# PLA_LED_Gen2_Rev4.net
KiCad netlist of a schematic drawn in EAGLE
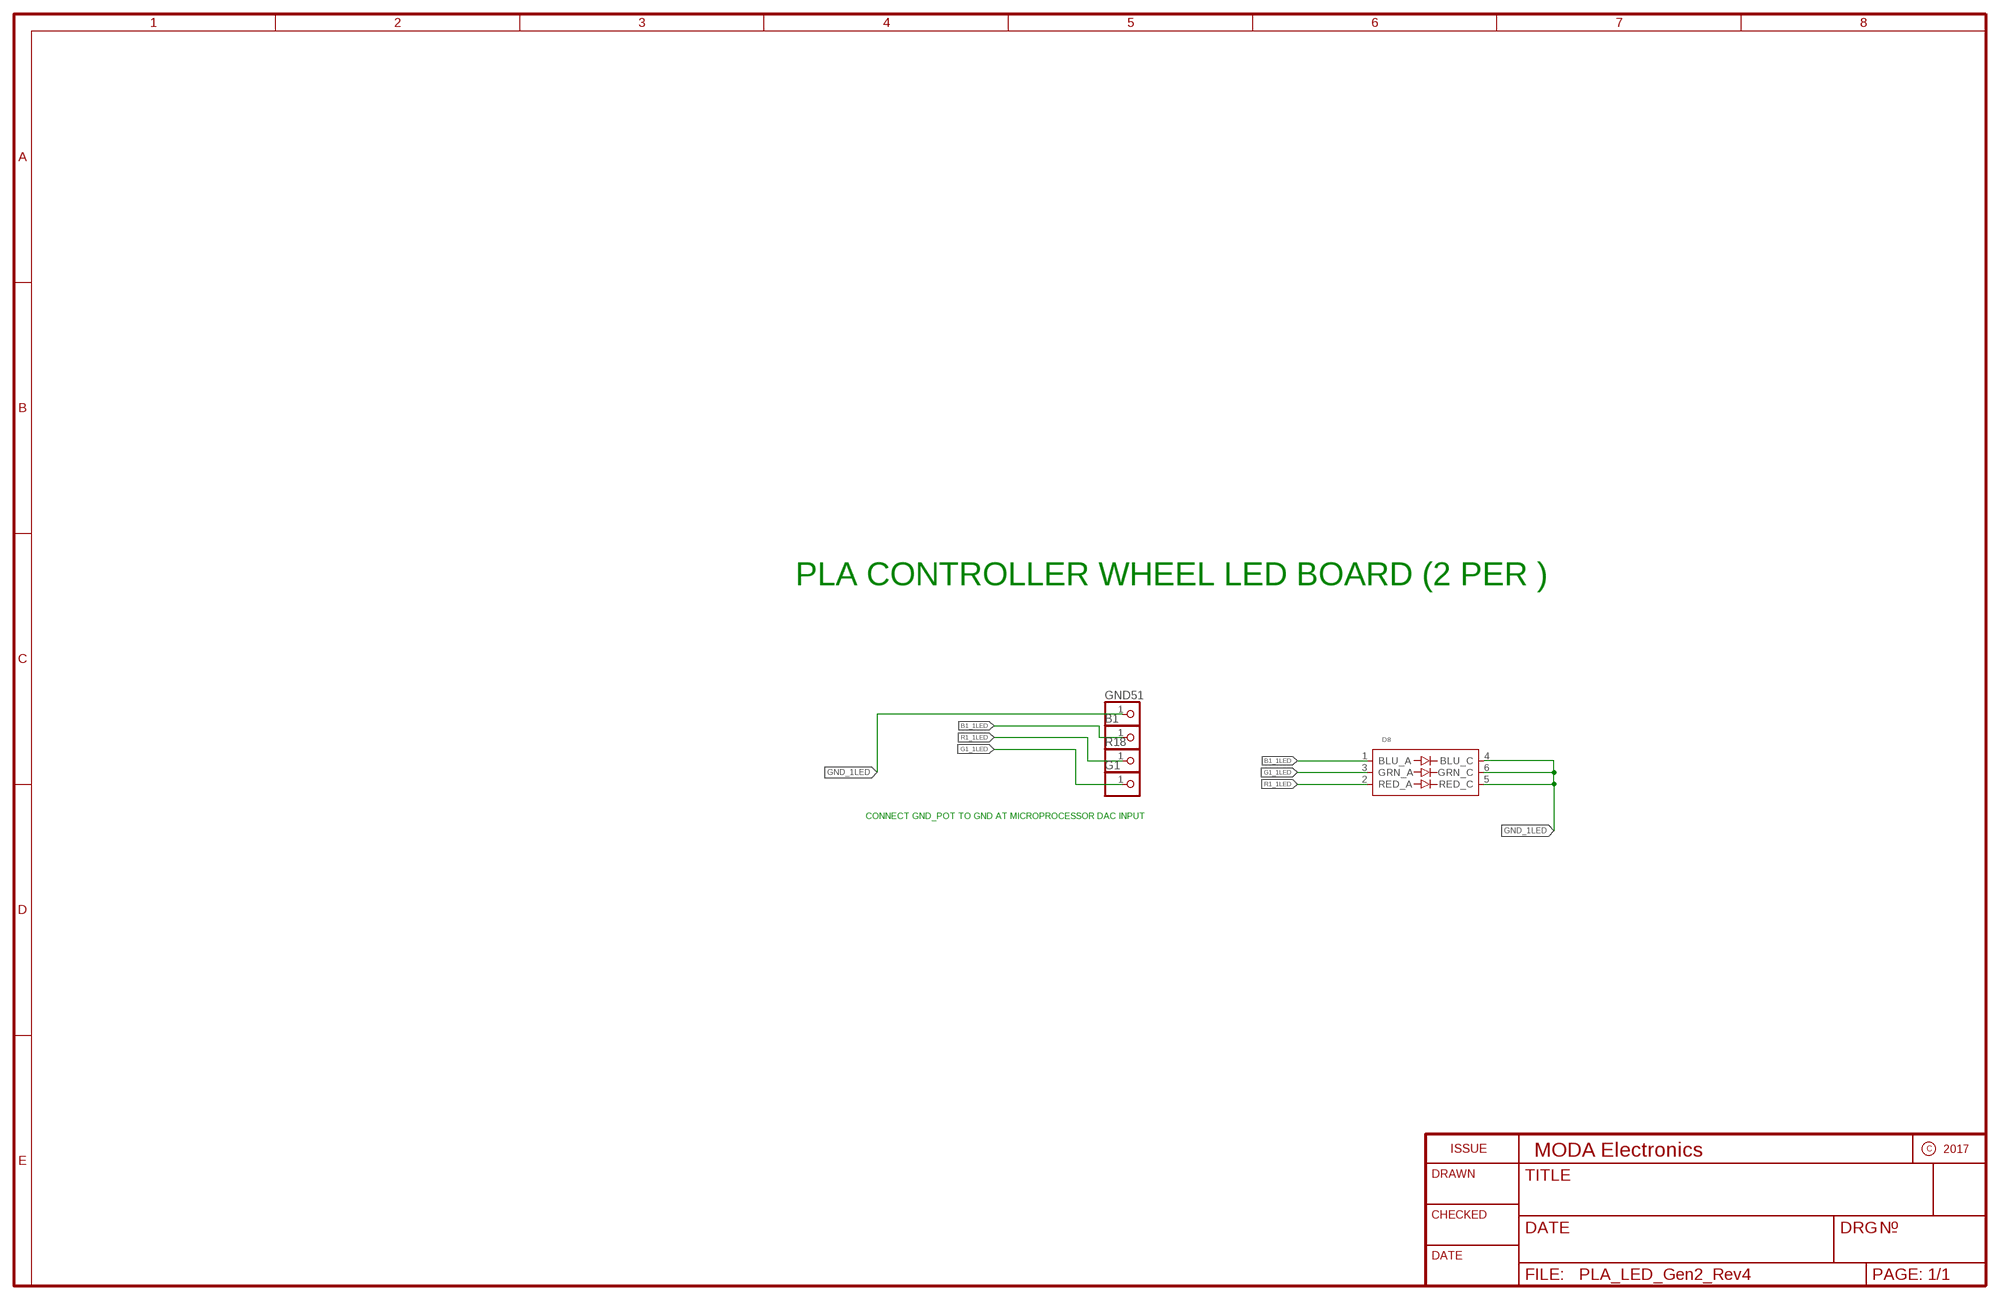
[diagram p0: schematic, sheet 1]

(export (version "E")
  (design (tool "Eeschema 10.0.6"))
  (components
    (comp (ref "B1")
      (value "PINHD-1X1")
      (footprint "eagle-import:1X01")
      (libsource (lib "eagle-import") (part "PINHD-1X1"))
    )
    (comp (ref "D8")
      (value "XZFBBM2ACRDG92W-3")
      (footprint "eagle-import:XZFBBM2ACRDG92W-3")
      (libsource (lib "eagle-import") (part "XZFBBM2ACRDG92W-3"))
    )
    (comp (ref "G1")
      (value "PINHD-1X1")
      (footprint "eagle-import:1X01")
      (libsource (lib "eagle-import") (part "PINHD-1X1"))
    )
    (comp (ref "GND51")
      (value "PINHD-1X1")
      (footprint "eagle-import:1X01")
      (libsource (lib "eagle-import") (part "PINHD-1X1"))
    )
    (comp (ref "R18")
      (value "PINHD-1X1")
      (footprint "eagle-import:1X01")
      (libsource (lib "eagle-import") (part "PINHD-1X1"))
    )
  )
  (nets
    (net (code "1") (name "B1_1LED") (class "Default")
      (node (ref "B1") (pin "1") (pinfunction "1_1") (pintype "passive"))
      (node (ref "D8") (pin "1") (pinfunction "BLU_A_1") (pintype "bidirectional"))
    )
    (net (code "2") (name "G1_1LED") (class "Default")
      (node (ref "D8") (pin "3") (pinfunction "GRN_A_3") (pintype "bidirectional"))
      (node (ref "G1") (pin "1") (pinfunction "1_1") (pintype "passive"))
    )
    (net (code "3") (name "GND_1LED") (class "Default")
      (node (ref "D8") (pin "4") (pinfunction "BLU_C_4") (pintype "bidirectional"))
      (node (ref "D8") (pin "5") (pinfunction "RED_C_5") (pintype "bidirectional"))
      (node (ref "D8") (pin "6") (pinfunction "GRN_C_6") (pintype "bidirectional"))
      (node (ref "GND51") (pin "1") (pinfunction "1_1") (pintype "passive"))
    )
    (net (code "4") (name "R1_1LED") (class "Default")
      (node (ref "D8") (pin "2") (pinfunction "RED_A_2") (pintype "bidirectional"))
      (node (ref "R18") (pin "1") (pinfunction "1_1") (pintype "passive"))
    )
  )
)
